# 02_Power.net
KiCad netlist of a schematic drawn in Altium Designer
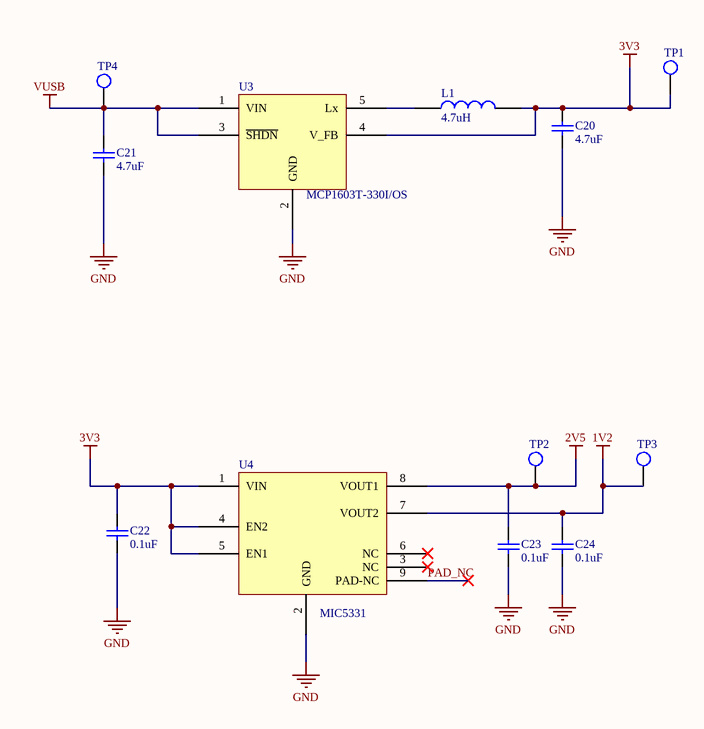
[diagram p0: 02_Power.SchDoc]

(export (version "E")
  (design (tool "Eeschema 10.0.6"))
  (components
    (comp (ref "C20")
      (value "4.7uF")
      (footprint "CAP0805R")
      (description "Capacitor")
      (libsource (lib "Quatro_SchLib") (part "C"))
    )
    (comp (ref "C21")
      (value "4.7uF")
      (footprint "CAP0805R")
      (description "Capacitor")
      (libsource (lib "Quatro_SchLib") (part "C"))
    )
    (comp (ref "C22")
      (value "0.1uF")
      (footprint "CAP0402R")
      (description "Capacitor")
      (libsource (lib "Quatro_SchLib") (part "C"))
    )
    (comp (ref "C23")
      (value "0.1uF")
      (footprint "CAP0402R")
      (description "Capacitor")
      (libsource (lib "Quatro_SchLib") (part "C"))
    )
    (comp (ref "C24")
      (value "0.1uF")
      (footprint "CAP0402R")
      (description "Capacitor")
      (libsource (lib "Quatro_SchLib") (part "C"))
    )
    (comp (ref "L1")
      (value "4.7uH")
      (footprint "744031004")
      (description "Inductor")
      (libsource (lib "Quatro_SchLib") (part "L"))
    )
    (comp (ref "TP1")
      (value "TestPoint")
      (footprint "TestPoint")
      (description "Test Point")
      (libsource (lib "Quatro_SchLib") (part "TestPoint"))
    )
    (comp (ref "TP2")
      (value "TestPoint")
      (footprint "TestPoint")
      (description "Test Point")
      (libsource (lib "Quatro_SchLib") (part "TestPoint"))
    )
    (comp (ref "TP3")
      (value "TestPoint")
      (footprint "TestPoint")
      (description "Test Point")
      (libsource (lib "Quatro_SchLib") (part "TestPoint"))
    )
    (comp (ref "TP4")
      (value "TestPoint")
      (footprint "TestPoint")
      (description "Test Point")
      (libsource (lib "Quatro_SchLib") (part "TestPoint"))
    )
    (comp (ref "U3")
      (value "MCP1603T-330I/OS")
      (footprint "SOT23-5")
      (description "3.3V 500mA Buck Converter")
      (fields (field (name "PUBLISHER") "MUEEC"))
      (libsource (lib "Quatro_SchLib") (part "MCP1603T-330I/OS"))
    )
    (comp (ref "U4")
      (value "MIC5331")
      (footprint "TDFN22")
      (description "1.2V, 2.5V 300mA LDO")
      (libsource (lib "Quatro_SchLib") (part "MIC5331"))
    )
  )
  (nets
    (net (code "1") (name "/PAD_NC") (class "Default")
      (node (ref "U4") (pin "9") (pinfunction "PAD-NC_9") (pintype "passive+no_connect"))
    )
    (net (code "2") (name "1V2") (class "Default")
      (node (ref "C24") (pin "1") (pinfunction "1_1") (pintype "passive"))
      (node (ref "TP3") (pin "0") (pinfunction "TP_0") (pintype "passive"))
      (node (ref "U4") (pin "7") (pinfunction "VOUT2_7") (pintype "passive"))
    )
    (net (code "3") (name "2V5") (class "Default")
      (node (ref "C23") (pin "1") (pinfunction "1_1") (pintype "passive"))
      (node (ref "TP2") (pin "0") (pinfunction "TP_0") (pintype "passive"))
      (node (ref "U4") (pin "8") (pinfunction "VOUT1_8") (pintype "passive"))
    )
    (net (code "4") (name "3V3") (class "Default")
      (node (ref "C20") (pin "1") (pinfunction "1_1") (pintype "passive"))
      (node (ref "C22") (pin "1") (pinfunction "1_1") (pintype "passive"))
      (node (ref "L1") (pin "2") (pinfunction "2_2") (pintype "passive"))
      (node (ref "TP1") (pin "0") (pinfunction "TP_0") (pintype "passive"))
      (node (ref "U3") (pin "4") (pinfunction "V_FB_4") (pintype "passive"))
      (node (ref "U4") (pin "1") (pinfunction "VIN_1") (pintype "passive"))
      (node (ref "U4") (pin "4") (pinfunction "EN2_4") (pintype "passive"))
      (node (ref "U4") (pin "5") (pinfunction "EN1_5") (pintype "passive"))
    )
    (net (code "5") (name "GND") (class "Default")
      (node (ref "C20") (pin "2") (pinfunction "2_2") (pintype "passive"))
      (node (ref "C21") (pin "2") (pinfunction "2_2") (pintype "passive"))
      (node (ref "C22") (pin "2") (pinfunction "2_2") (pintype "passive"))
      (node (ref "C23") (pin "2") (pinfunction "2_2") (pintype "passive"))
      (node (ref "C24") (pin "2") (pinfunction "2_2") (pintype "passive"))
      (node (ref "U3") (pin "2") (pinfunction "GND_2") (pintype "passive"))
      (node (ref "U4") (pin "2") (pinfunction "GND_2") (pintype "passive"))
    )
    (net (code "6") (name "Net-(U3-Lx)") (class "Default")
      (node (ref "L1") (pin "1") (pinfunction "1_1") (pintype "passive"))
      (node (ref "U3") (pin "5") (pinfunction "Lx_5") (pintype "passive"))
    )
    (net (code "7") (name "VUSB") (class "Default")
      (node (ref "C21") (pin "1") (pinfunction "1_1") (pintype "passive"))
      (node (ref "TP4") (pin "0") (pinfunction "TP_0") (pintype "passive"))
      (node (ref "U3") (pin "1") (pinfunction "VIN_1") (pintype "passive"))
      (node (ref "U3") (pin "3") (pinfunction "~{SHDN}_3") (pintype "passive"))
    )
    (net (code "8") (name "unconnected-(U4-NC-Pad3)") (class "Default")
      (node (ref "U4") (pin "3") (pinfunction "NC_3") (pintype "passive+no_connect"))
    )
    (net (code "9") (name "unconnected-(U4-NC-Pad6)") (class "Default")
      (node (ref "U4") (pin "6") (pinfunction "NC_6") (pintype "passive+no_connect"))
    )
  )
)
